# Fri3D_2018_CONTROLLER_00.net
KiCad netlist of a schematic drawn in Altium Designer
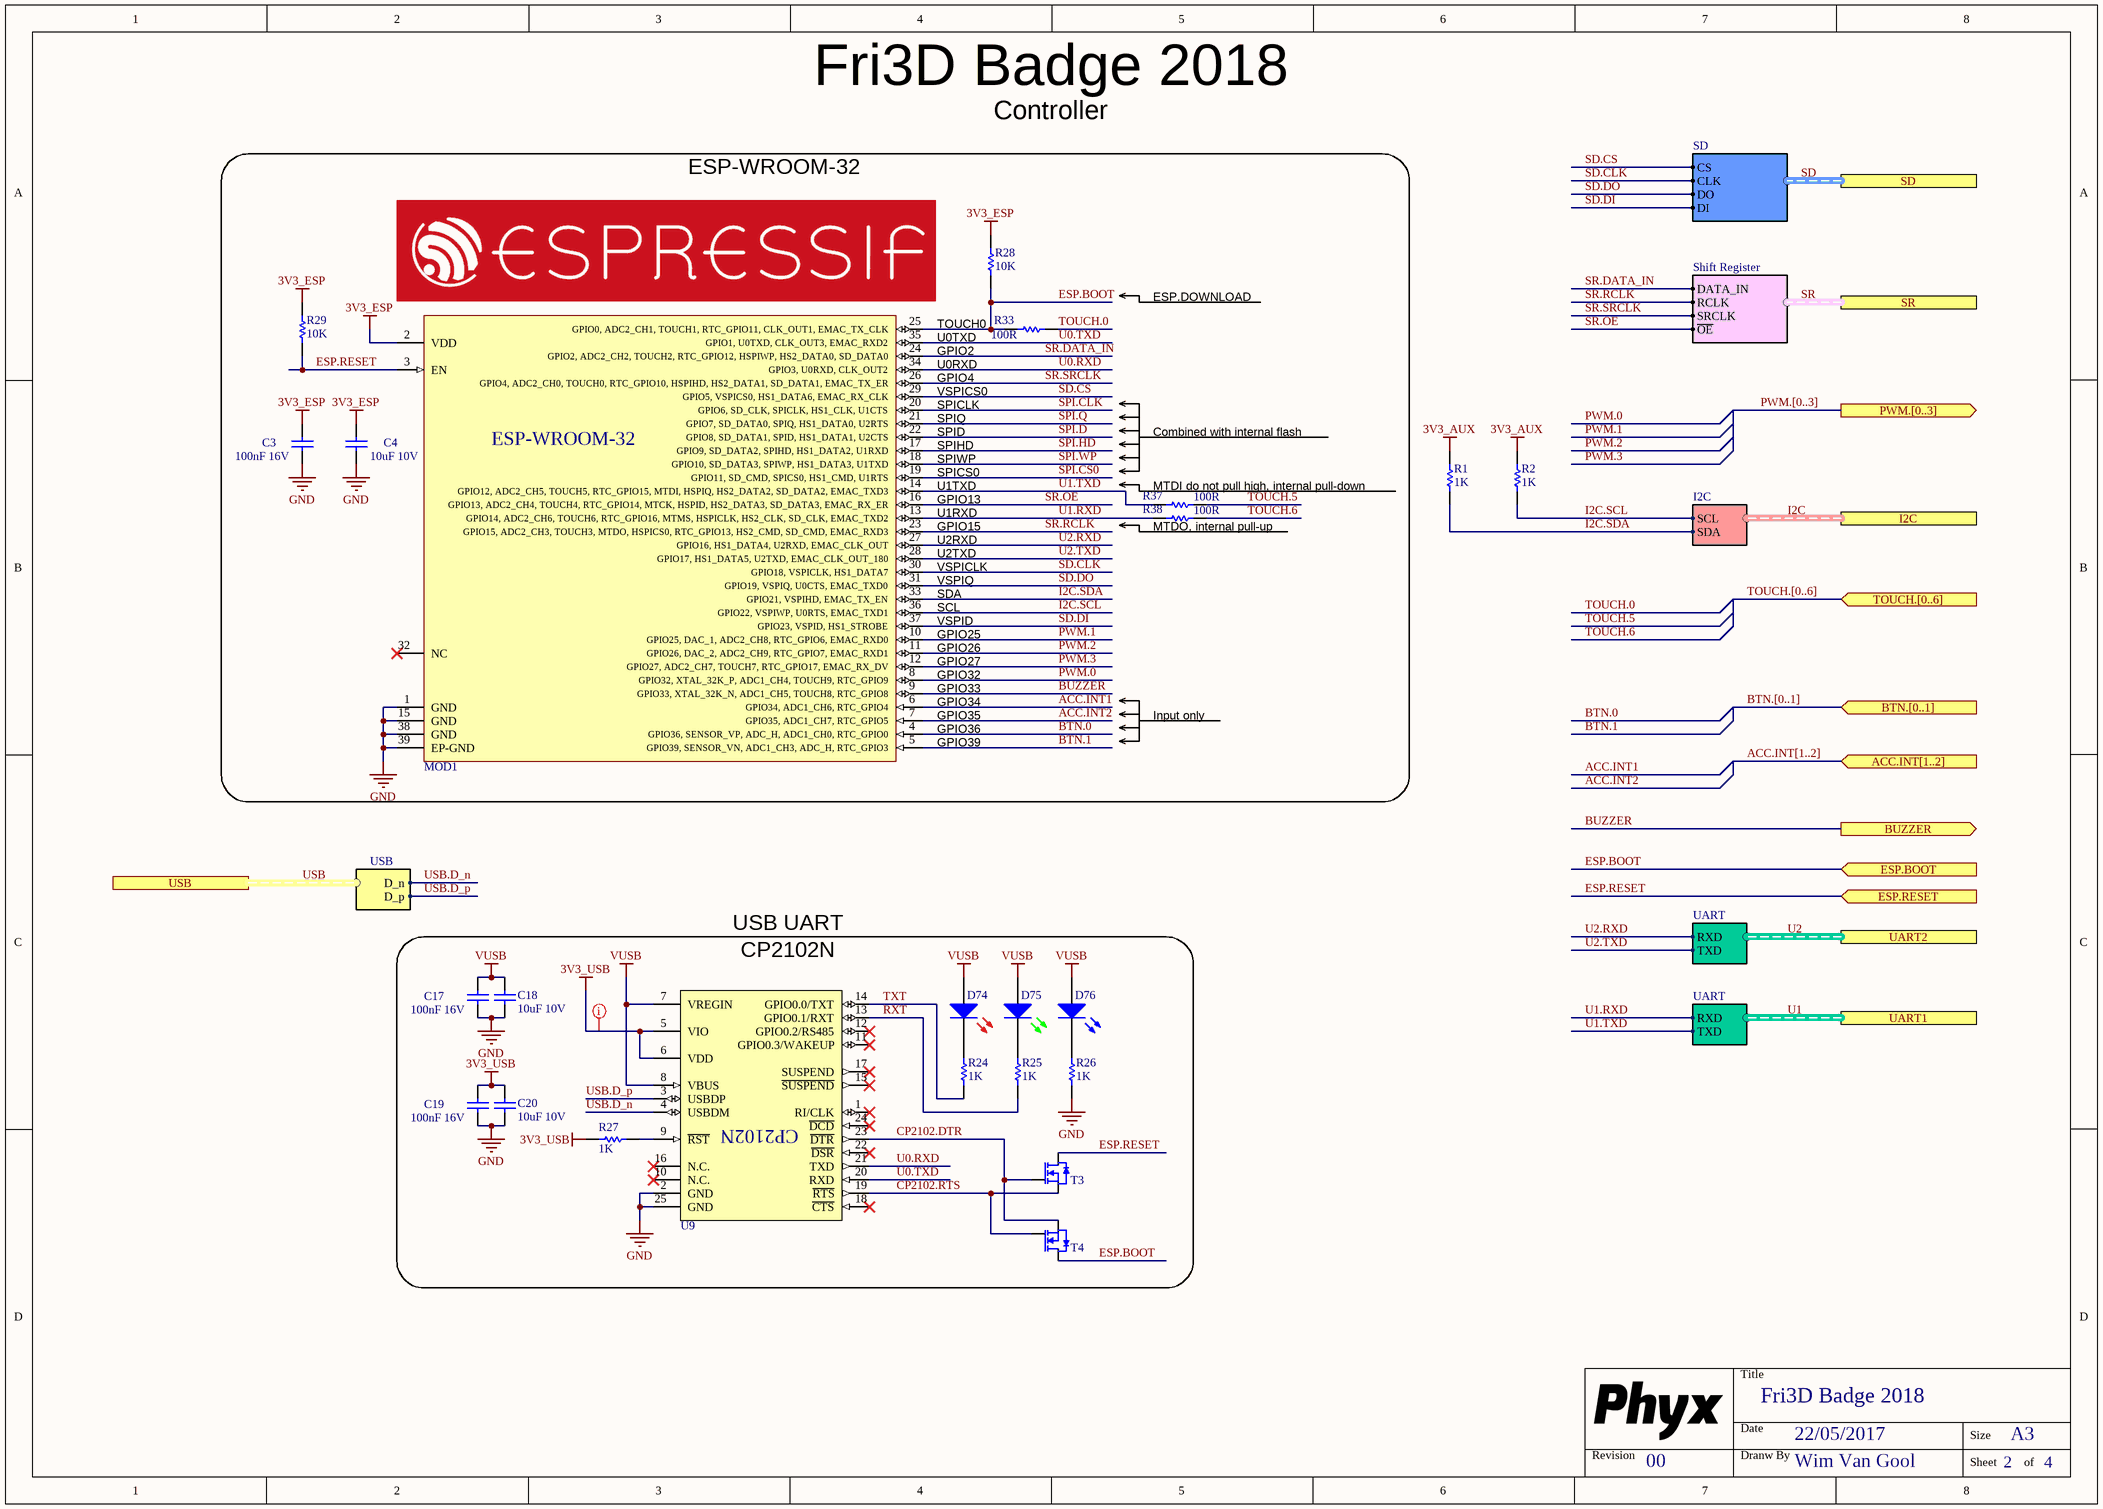
[diagram p0: Fri3D_2018_CONTROLLER_00.SchDoc]

(export (version "E")
  (design (tool "Eeschema 10.0.6"))
  (components
    (comp (ref "C3")
      (value "100nF 16V")
      (footprint "C0603_N")
      (description "Capacitor Ceramic")
      (libsource (lib "Phyx_Components") (part "CAP_CERAMIC"))
    )
    (comp (ref "C4")
      (value "10uF 10V")
      (footprint "C0805_N")
      (description "Capacitor Ceramic")
      (fields (field (name "Comment") "CAP_CERAMIC"))
      (libsource (lib "Phyx_Components") (part "CAP_CERAMIC"))
    )
    (comp (ref "C17")
      (value "100nF 16V")
      (footprint "C0603_N")
      (description "Capacitor Ceramic")
      (libsource (lib "Phyx_Components") (part "CAP_CERAMIC"))
    )
    (comp (ref "C18")
      (value "10uF 10V")
      (footprint "C0805_N")
      (description "Capacitor Ceramic")
      (fields (field (name "Comment") "CAP_CERAMIC"))
      (libsource (lib "Phyx_Components") (part "CAP_CERAMIC"))
    )
    (comp (ref "C19")
      (value "100nF 16V")
      (footprint "C0603_N")
      (description "Capacitor Ceramic")
      (libsource (lib "Phyx_Components") (part "CAP_CERAMIC"))
    )
    (comp (ref "C20")
      (value "10uF 10V")
      (footprint "C0805_N")
      (description "Capacitor Ceramic")
      (fields (field (name "Comment") "CAP_CERAMIC"))
      (libsource (lib "Phyx_Components") (part "CAP_CERAMIC"))
    )
    (comp (ref "D74")
      (value "Default 0805 Red LED")
      (footprint "LED_0805_RD")
      (description "=Description")
      (libsource (lib "Phyx_Components") (part "LED_RED"))
    )
    (comp (ref "D75")
      (value "Default 0805 Green LED")
      (footprint "LED_0805_GR")
      (description "=Description")
      (libsource (lib "Phyx_Components") (part "LED_GREEN"))
    )
    (comp (ref "D76")
      (value "Default 0805 Blue LED")
      (footprint "LED_0805_BL")
      (description "=Description")
      (libsource (lib "Phyx_Components") (part "LED_BLUE"))
    )
    (comp (ref "MOD1")
      (value "ESP-32 based ESP-WROOM-32")
      (footprint "ESP-WROOM-32")
      (description "WiFi # MOD ESP-WROOM-32")
      (libsource (lib "Phyx_Components") (part "ESP-WROOM-32"))
    )
    (comp (ref "R1") (value "1K") (footprint "R0603_N") (libsource (lib "Phyx_Components") (part "RESISTOR")))
    (comp (ref "R2") (value "1K") (footprint "R0603_N") (libsource (lib "Phyx_Components") (part "RESISTOR")))
    (comp (ref "R24")
      (value "1K")
      (footprint "R0603_N")
      (libsource (lib "Phyx_Components") (part "RESISTOR"))
    )
    (comp (ref "R25")
      (value "1K")
      (footprint "R0603_N")
      (libsource (lib "Phyx_Components") (part "RESISTOR"))
    )
    (comp (ref "R26")
      (value "1K")
      (footprint "R0603_N")
      (libsource (lib "Phyx_Components") (part "RESISTOR"))
    )
    (comp (ref "R27")
      (value "1K")
      (footprint "R0603_N")
      (libsource (lib "Phyx_Components") (part "RESISTOR"))
    )
    (comp (ref "R28")
      (value "10K")
      (footprint "R0603_N")
      (fields (field (name "Comment") "RESISTOR"))
      (libsource (lib "Phyx_Components") (part "RESISTOR"))
    )
    (comp (ref "R29")
      (value "10K")
      (footprint "R0603_N")
      (fields (field (name "Comment") "RESISTOR"))
      (libsource (lib "Phyx_Components") (part "RESISTOR"))
    )
    (comp (ref "R33")
      (value "100R")
      (footprint "R0603_N")
      (fields (field (name "Comment") "RESISTOR"))
      (libsource (lib "Phyx_Components") (part "RESISTOR"))
    )
    (comp (ref "R37")
      (value "100R")
      (footprint "R0603_N")
      (fields (field (name "Comment") "RESISTOR"))
      (libsource (lib "Phyx_Components") (part "RESISTOR"))
    )
    (comp (ref "R38")
      (value "100R")
      (footprint "R0603_N")
      (fields (field (name "Comment") "RESISTOR"))
      (libsource (lib "Phyx_Components") (part "RESISTOR"))
    )
    (comp (ref "T3")
      (value "0.2A N-Ch MOSFET Vgs 3.2")
      (footprint "SOT23-3")
      (libsource (lib "Phyx_Components") (part "N_MOSFET_GSD"))
    )
    (comp (ref "T4")
      (value "0.2A N-Ch MOSFET Vgs 3.2")
      (footprint "SOT23-3")
      (libsource (lib "Phyx_Components") (part "N_MOSFET_GSD"))
    )
    (comp (ref "U9")
      (value "USB to UART 3.3-5V")
      (footprint "QFN_24")
      (description "=Description")
      (libsource (lib "Phyx_Components") (part "CP2102N_QFN24"))
    )
  )
  (nets
    (net (code "12") (name "/ACC.INT1") (class "Default")
      (node (ref "MOD1") (pin "6") (pinfunction "GPIO34,_ADC1_CH6,_RTC_GPIO4_6") (pintype "input"))
    )
    (net (code "13") (name "/ACC.INT2") (class "Default")
      (node (ref "MOD1") (pin "7") (pinfunction "GPIO35,_ADC1_CH7,_RTC_GPIO5_7") (pintype "input"))
    )
    (net (code "15") (name "/BTN.0") (class "Default")
      (node (ref "MOD1") (pin "4") (pinfunction "GPIO36,_SENSOR_VP,_ADC_H,_ADC1_CH0,_RTC_GPIO0_4") (pintype "input"))
    )
    (net (code "16") (name "/BTN.1") (class "Default")
      (node (ref "MOD1") (pin "5") (pinfunction "GPIO39,_SENSOR_VN,_ADC1_CH3,_ADC_H,_RTC_GPIO3_5") (pintype "input"))
    )
    (net (code "18") (name "/BUZZER") (class "Default")
      (node (ref "MOD1") (pin "9") (pinfunction "GPIO33,_XTAL_32K_N,_ADC1_CH5,_TOUCH8,_RTC_GPIO8_9") (pintype "bidirectional"))
    )
    (net (code "19") (name "/CP2102.DTR") (class "Default")
      (node (ref "T3") (pin "1") (pinfunction "G_1") (pintype "passive"))
      (node (ref "T4") (pin "2") (pinfunction "S_2") (pintype "passive"))
      (node (ref "U9") (pin "23") (pinfunction "~{DTR}_23") (pintype "output"))
    )
    (net (code "20") (name "/CP2102.RTS") (class "Default")
      (node (ref "T3") (pin "2") (pinfunction "S_2") (pintype "passive"))
      (node (ref "T4") (pin "1") (pinfunction "G_1") (pintype "passive"))
      (node (ref "U9") (pin "19") (pinfunction "~{RTS}_19") (pintype "output"))
    )
    (net (code "21") (name "/ESP.BOOT") (class "Default")
      (node (ref "MOD1") (pin "25") (pinfunction "GPIO0,_ADC2_CH1,_TOUCH1,_RTC_GPIO11,_CLK_OUT1,_EMAC_TX_CLK_25") (pintype "bidirectional"))
      (node (ref "R28") (pin "2") (pinfunction "2_2") (pintype "passive"))
      (node (ref "R33") (pin "1") (pinfunction "1_1") (pintype "passive"))
      (node (ref "T4") (pin "3") (pinfunction "D_3") (pintype "passive"))
    )
    (net (code "22") (name "/ESP.RESET") (class "Default")
      (node (ref "MOD1") (pin "3") (pinfunction "EN_3") (pintype "input"))
      (node (ref "R29") (pin "2") (pinfunction "2_2") (pintype "passive"))
      (node (ref "T3") (pin "3") (pinfunction "D_3") (pintype "passive"))
    )
    (net (code "23") (name "/I2C.SCL") (class "Default")
      (node (ref "MOD1") (pin "36") (pinfunction "GPIO22,_VSPIWP,_U0RTS,_EMAC_TXD1_36") (pintype "bidirectional"))
      (node (ref "R2") (pin "2") (pinfunction "2_2") (pintype "passive"))
    )
    (net (code "24") (name "/I2C.SDA") (class "Default")
      (node (ref "MOD1") (pin "33") (pinfunction "GPIO21,_VSPIHD,_EMAC_TX_EN_33") (pintype "bidirectional"))
      (node (ref "R1") (pin "2") (pinfunction "2_2") (pintype "passive"))
    )
    (net (code "26") (name "/PWM.0") (class "Default")
      (node (ref "MOD1") (pin "8") (pinfunction "GPIO32,_XTAL_32K_P,_ADC1_CH4,_TOUCH9,_RTC_GPIO9_8") (pintype "bidirectional"))
    )
    (net (code "27") (name "/PWM.1") (class "Default")
      (node (ref "MOD1") (pin "10") (pinfunction "GPIO25,_DAC_1,_ADC2_CH8,_RTC_GPIO6,_EMAC_RXD0_10") (pintype "bidirectional"))
    )
    (net (code "28") (name "/PWM.2") (class "Default")
      (node (ref "MOD1") (pin "11") (pinfunction "GPIO26,_DAC_2,_ADC2_CH9,_RTC_GPIO7,_EMAC_RXD1_11") (pintype "bidirectional"))
    )
    (net (code "29") (name "/PWM.3") (class "Default")
      (node (ref "MOD1") (pin "12") (pinfunction "GPIO27,_ADC2_CH7,_TOUCH7,_RTC_GPIO17,_EMAC_RX_DV_12") (pintype "bidirectional"))
    )
    (net (code "31") (name "/RXT") (class "Default")
      (node (ref "R25") (pin "2") (pinfunction "2_2") (pintype "passive"))
      (node (ref "U9") (pin "13") (pinfunction "GPIO0.1/RXT_13") (pintype "bidirectional"))
    )
    (net (code "32") (name "/SD.CLK") (class "Default")
      (node (ref "MOD1") (pin "30") (pinfunction "GPIO18,_VSPICLK,_HS1_DATA7_30") (pintype "bidirectional"))
    )
    (net (code "33") (name "/SD.CS") (class "Default")
      (node (ref "MOD1") (pin "29") (pinfunction "GPIO5,_VSPICS0,_HS1_DATA6,_EMAC_RX_CLK_29") (pintype "bidirectional"))
    )
    (net (code "34") (name "/SD.DI") (class "Default")
      (node (ref "MOD1") (pin "37") (pinfunction "GPIO23,_VSPID,_HS1_STROBE_37") (pintype "bidirectional"))
    )
    (net (code "35") (name "/SD.DO") (class "Default")
      (node (ref "MOD1") (pin "31") (pinfunction "GPIO19,_VSPIQ,_U0CTS,_EMAC_TXD0_31") (pintype "bidirectional"))
    )
    (net (code "37") (name "/SPI.CLK") (class "Default")
      (node (ref "MOD1") (pin "20") (pinfunction "GPIO6,_SD_CLK,_SPICLK,_HS1_CLK,_U1CTS_20") (pintype "bidirectional"))
    )
    (net (code "38") (name "/SPI.CS0") (class "Default")
      (node (ref "MOD1") (pin "19") (pinfunction "GPIO11,_SD_CMD,_SPICS0,_HS1_CMD,_U1RTS_19") (pintype "bidirectional"))
    )
    (net (code "39") (name "/SPI.D") (class "Default")
      (node (ref "MOD1") (pin "22") (pinfunction "GPIO8,_SD_DATA1,_SPID,_HS1_DATA1,_U2CTS_22") (pintype "bidirectional"))
    )
    (net (code "40") (name "/SPI.HD") (class "Default")
      (node (ref "MOD1") (pin "17") (pinfunction "GPIO9,_SD_DATA2,_SPIHD,_HS1_DATA2,_U1RXD_17") (pintype "bidirectional"))
    )
    (net (code "41") (name "/SPI.Q") (class "Default")
      (node (ref "MOD1") (pin "21") (pinfunction "GPIO7,_SD_DATA0,_SPIQ,_HS1_DATA0,_U2RTS_21") (pintype "bidirectional"))
    )
    (net (code "42") (name "/SPI.WP") (class "Default")
      (node (ref "MOD1") (pin "18") (pinfunction "GPIO10,_SD_DATA3,_SPIWP,_HS1_DATA3,_U1TXD_18") (pintype "bidirectional"))
    )
    (net (code "43") (name "/SR.DATA_IN") (class "Default")
      (node (ref "MOD1") (pin "24") (pinfunction "GPIO2,_ADC2_CH2,_TOUCH2,_RTC_GPIO12,_HSPIWP,_HS2_DATA0,_SD_DATA0_24") (pintype "bidirectional"))
    )
    (net (code "44") (name "/SR.RCLK") (class "Default")
      (node (ref "MOD1") (pin "23") (pinfunction "GPIO15,_ADC2_CH3,_TOUCH3,_MTDO,_HSPICS0,_RTC_GPIO13,_HS2_CMD,_SD_CMD,_EMAC_RXD3_23") (pintype "bidirectional"))
    )
    (net (code "45") (name "/SR.SRCLK") (class "Default")
      (node (ref "MOD1") (pin "26") (pinfunction "GPIO4,_ADC2_CH0,_TOUCH0,_RTC_GPIO10,_HSPIHD,_HS2_DATA1,_SD_DATA1,_EMAC_TX_ER_26") (pintype "bidirectional"))
    )
    (net (code "46") (name "/SR.~{OE}") (class "Default")
      (node (ref "MOD1") (pin "16") (pinfunction "GPIO13,_ADC2_CH4,_TOUCH4,_RTC_GPIO14,_MTCK,_HSPID,_HS2_DATA3,_SD_DATA3,_EMAC_RX_ER_16") (pintype "bidirectional"))
    )
    (net (code "48") (name "/TOUCH.0") (class "Default")
      (node (ref "R33") (pin "2") (pinfunction "2_2") (pintype "passive"))
    )
    (net (code "49") (name "/TOUCH.5") (class "Default")
      (node (ref "R37") (pin "2") (pinfunction "2_2") (pintype "passive"))
    )
    (net (code "50") (name "/TOUCH.6") (class "Default")
      (node (ref "R38") (pin "2") (pinfunction "2_2") (pintype "passive"))
    )
    (net (code "52") (name "/TXT") (class "Default")
      (node (ref "R24") (pin "2") (pinfunction "2_2") (pintype "passive"))
      (node (ref "U9") (pin "14") (pinfunction "GPIO0.0/TXT_14") (pintype "bidirectional"))
    )
    (net (code "53") (name "/U0.RXD") (class "Default")
      (node (ref "MOD1") (pin "34") (pinfunction "GPIO3,_U0RXD,_CLK_OUT2_34") (pintype "bidirectional"))
      (node (ref "U9") (pin "21") (pinfunction "TXD_21") (pintype "output"))
    )
    (net (code "54") (name "/U0.TXD") (class "Default")
      (node (ref "MOD1") (pin "35") (pinfunction "GPIO1,_U0TXD,_CLK_OUT3,_EMAC_RXD2_35") (pintype "bidirectional"))
      (node (ref "U9") (pin "20") (pinfunction "RXD_20") (pintype "input"))
    )
    (net (code "55") (name "/U1.RXD") (class "Default")
      (node (ref "MOD1") (pin "13") (pinfunction "GPIO14,_ADC2_CH6,_TOUCH6,_RTC_GPIO16,_MTMS,_HSPICLK,_HS2_CLK,_SD_CLK,_EMAC_TXD2_13") (pintype "bidirectional"))
      (node (ref "R38") (pin "1") (pinfunction "1_1") (pintype "passive"))
    )
    (net (code "56") (name "/U1.TXD") (class "Default")
      (node (ref "MOD1") (pin "14") (pinfunction "GPIO12,_ADC2_CH5,_TOUCH5,_RTC_GPIO15,_MTDI,_HSPIQ,_HS2_DATA2,_SD_DATA2,_EMAC_TXD3_14") (pintype "bidirectional"))
      (node (ref "R37") (pin "1") (pinfunction "1_1") (pintype "passive"))
    )
    (net (code "58") (name "/U2.RXD") (class "Default")
      (node (ref "MOD1") (pin "27") (pinfunction "GPIO16,_HS1_DATA4,_U2RXD,_EMAC_CLK_OUT_27") (pintype "bidirectional"))
    )
    (net (code "59") (name "/U2.TXD") (class "Default")
      (node (ref "MOD1") (pin "28") (pinfunction "GPIO17,_HS1_DATA5,_U2TXD,_EMAC_CLK_OUT_180_28") (pintype "bidirectional"))
    )
    (net (code "61") (name "/USB.D_n") (class "Default")
      (node (ref "U9") (pin "4") (pinfunction "USBDM_4") (pintype "bidirectional"))
    )
    (net (code "62") (name "/USB.D_p") (class "Default")
      (node (ref "U9") (pin "3") (pinfunction "USBDP_3") (pintype "bidirectional"))
    )
    (net (code "64") (name "3V3_AUX") (class "Default")
      (node (ref "R1") (pin "1") (pinfunction "1_1") (pintype "passive"))
      (node (ref "R2") (pin "1") (pinfunction "1_1") (pintype "passive"))
    )
    (net (code "65") (name "3V3_ESP") (class "Default")
      (node (ref "C3") (pin "1") (pinfunction "1_1") (pintype "passive"))
      (node (ref "C4") (pin "1") (pinfunction "1_1") (pintype "passive"))
      (node (ref "MOD1") (pin "2") (pinfunction "VDD_2") (pintype "power_in"))
      (node (ref "R28") (pin "1") (pinfunction "1_1") (pintype "passive"))
      (node (ref "R29") (pin "1") (pinfunction "1_1") (pintype "passive"))
    )
    (net (code "66") (name "3V3_USB") (class "Default")
      (node (ref "C19") (pin "1") (pinfunction "1_1") (pintype "passive"))
      (node (ref "C20") (pin "2") (pinfunction "2_2") (pintype "passive"))
      (node (ref "R27") (pin "1") (pinfunction "1_1") (pintype "passive"))
      (node (ref "U9") (pin "5") (pinfunction "VIO_5") (pintype "power_in"))
      (node (ref "U9") (pin "6") (pinfunction "VDD_6") (pintype "power_in"))
    )
    (net (code "67") (name "GND") (class "Default")
      (node (ref "C17") (pin "2") (pinfunction "2_2") (pintype "passive"))
      (node (ref "C18") (pin "1") (pinfunction "1_1") (pintype "passive"))
      (node (ref "C19") (pin "2") (pinfunction "2_2") (pintype "passive"))
      (node (ref "C20") (pin "1") (pinfunction "1_1") (pintype "passive"))
      (node (ref "C3") (pin "2") (pinfunction "2_2") (pintype "passive"))
      (node (ref "C4") (pin "2") (pinfunction "2_2") (pintype "passive"))
      (node (ref "MOD1") (pin "1") (pinfunction "GND_1") (pintype "power_in"))
      (node (ref "MOD1") (pin "15") (pinfunction "GND_15") (pintype "power_in"))
      (node (ref "MOD1") (pin "38") (pinfunction "GND_38") (pintype "power_in"))
      (node (ref "MOD1") (pin "39") (pinfunction "EP-GND_39") (pintype "power_in"))
      (node (ref "R26") (pin "2") (pinfunction "2_2") (pintype "passive"))
      (node (ref "U9") (pin "2") (pinfunction "GND_2") (pintype "power_in"))
      (node (ref "U9") (pin "25") (pinfunction "GND_25") (pintype "power_in"))
    )
    (net (code "68") (name "Net-(D74-K)") (class "Default")
      (node (ref "D74") (pin "2") (pinfunction "K_2") (pintype "passive"))
      (node (ref "R24") (pin "1") (pinfunction "1_1") (pintype "passive"))
    )
    (net (code "69") (name "Net-(D75-K)") (class "Default")
      (node (ref "D75") (pin "2") (pinfunction "K_2") (pintype "passive"))
      (node (ref "R25") (pin "1") (pinfunction "1_1") (pintype "passive"))
    )
    (net (code "70") (name "Net-(D76-K)") (class "Default")
      (node (ref "D76") (pin "2") (pinfunction "K_2") (pintype "passive"))
      (node (ref "R26") (pin "1") (pinfunction "1_1") (pintype "passive"))
    )
    (net (code "71") (name "Net-(U9-~{RST})") (class "Default")
      (node (ref "R27") (pin "2") (pinfunction "2_2") (pintype "passive"))
      (node (ref "U9") (pin "9") (pinfunction "~{RST}_9") (pintype "input"))
    )
    (net (code "72") (name "VUSB") (class "Default")
      (node (ref "C17") (pin "1") (pinfunction "1_1") (pintype "passive"))
      (node (ref "C18") (pin "2") (pinfunction "2_2") (pintype "passive"))
      (node (ref "D74") (pin "1") (pinfunction "A_1") (pintype "passive"))
      (node (ref "D75") (pin "1") (pinfunction "A_1") (pintype "passive"))
      (node (ref "D76") (pin "1") (pinfunction "A_1") (pintype "passive"))
      (node (ref "U9") (pin "7") (pinfunction "VREGIN_7") (pintype "power_in"))
      (node (ref "U9") (pin "8") (pinfunction "VBUS_8") (pintype "input"))
    )
    (net (code "73") (name "unconnected-(MOD1-NC-Pad32)") (class "Default")
      (node (ref "MOD1") (pin "32") (pinfunction "NC_32") (pintype "passive+no_connect"))
    )
    (net (code "74") (name "unconnected-(U9-GPIO0.2{slash}RS485-Pad12)") (class "Default")
      (node (ref "U9") (pin "12") (pinfunction "GPIO0.2/RS485_12") (pintype "bidirectional+no_connect"))
    )
    (net (code "75") (name "unconnected-(U9-GPIO0.3{slash}WAKEUP-Pad11)") (class "Default")
      (node (ref "U9") (pin "11") (pinfunction "GPIO0.3/WAKEUP_11") (pintype "bidirectional+no_connect"))
    )
    (net (code "76") (name "unconnected-(U9-N.C.-Pad10)") (class "Default")
      (node (ref "U9") (pin "10") (pinfunction "N.C._10") (pintype "passive+no_connect"))
    )
    (net (code "77") (name "unconnected-(U9-N.C.-Pad16)") (class "Default")
      (node (ref "U9") (pin "16") (pinfunction "N.C._16") (pintype "passive+no_connect"))
    )
    (net (code "78") (name "unconnected-(U9-RI{slash}CLK-Pad1)") (class "Default")
      (node (ref "U9") (pin "1") (pinfunction "RI/CLK_1") (pintype "bidirectional+no_connect"))
    )
    (net (code "79") (name "unconnected-(U9-SUSPEND-Pad17)") (class "Default")
      (node (ref "U9") (pin "17") (pinfunction "SUSPEND_17") (pintype "output+no_connect"))
    )
    (net (code "80") (name "unconnected-(U9-~{CTS}-Pad18)") (class "Default")
      (node (ref "U9") (pin "18") (pinfunction "~{CTS}_18") (pintype "input+no_connect"))
    )
    (net (code "81") (name "unconnected-(U9-~{DCD}-Pad24)") (class "Default")
      (node (ref "U9") (pin "24") (pinfunction "~{DCD}_24") (pintype "input+no_connect"))
    )
    (net (code "82") (name "unconnected-(U9-~{DSR}-Pad22)") (class "Default")
      (node (ref "U9") (pin "22") (pinfunction "~{DSR}_22") (pintype "input+no_connect"))
    )
    (net (code "83") (name "unconnected-(U9-~{SUSPEND}-Pad15)") (class "Default")
      (node (ref "U9") (pin "15") (pinfunction "~{SUSPEND}_15") (pintype "output+no_connect"))
    )
  )
)
